# Sprite.net
KiCad netlist of a schematic drawn in EAGLE
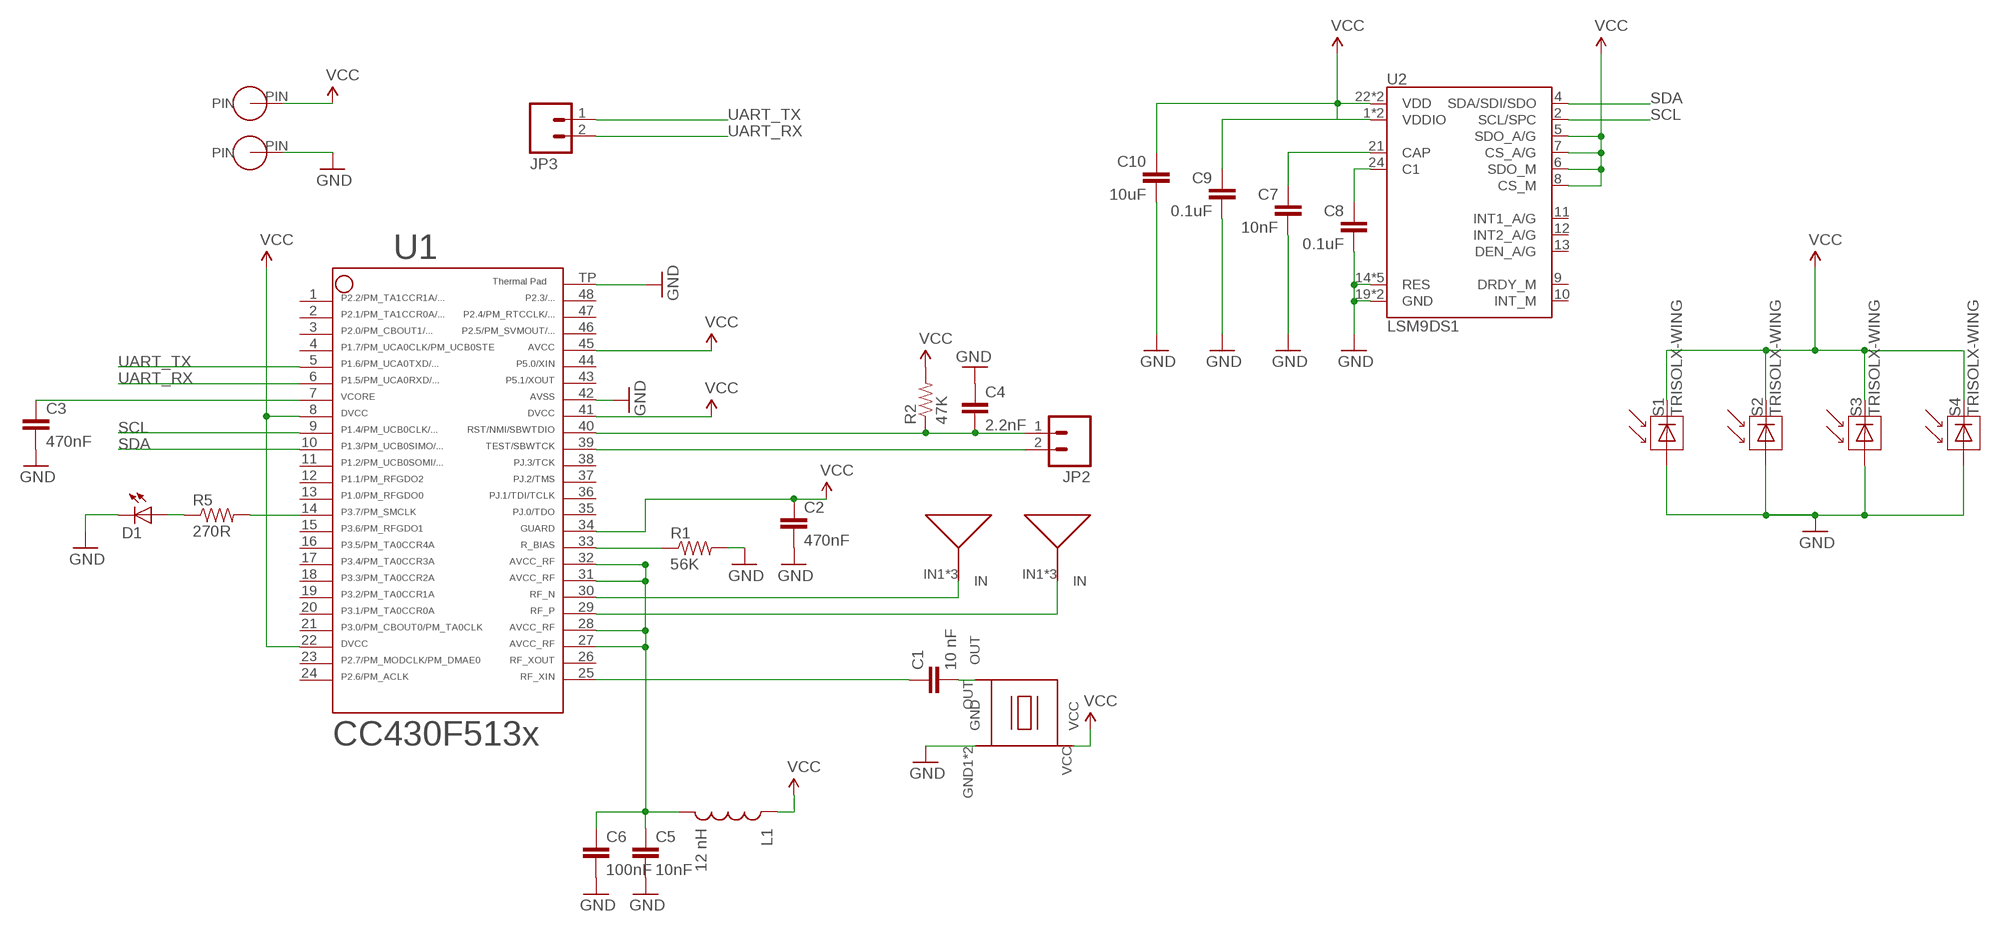
[diagram p0: schematic, sheet 1]

(export (version "E")
  (design (tool "Eeschema 10.0.6"))
  (components
    (comp (ref "ANT-N")
      (value "ANTENNA")
      (footprint "eagle-import:ANTENNA")
      (libsource (lib "eagle-import") (part "ANTENNA"))
    )
    (comp (ref "ANT-P")
      (value "ANTENNA")
      (footprint "eagle-import:ANTENNA")
      (libsource (lib "eagle-import") (part "ANTENNA"))
    )
    (comp (ref "C1")
      (value "10 nF")
      (footprint "eagle-import:0603-CAP")
      (libsource (lib "eagle-import") (part "CAP0603-CAP"))
    )
    (comp (ref "C2")
      (value "470nF")
      (footprint "eagle-import:0603-CAP")
      (libsource (lib "eagle-import") (part "CAP0603-CAP"))
    )
    (comp (ref "C3")
      (value "470nF")
      (footprint "eagle-import:0603-CAP")
      (libsource (lib "eagle-import") (part "CAP0603-CAP"))
    )
    (comp (ref "C4")
      (value "2.2nF")
      (footprint "eagle-import:0603-CAP")
      (libsource (lib "eagle-import") (part "CAP0603-CAP"))
    )
    (comp (ref "C5")
      (value "10nF")
      (footprint "eagle-import:0603-CAP")
      (libsource (lib "eagle-import") (part "CAP0603-CAP"))
    )
    (comp (ref "C6")
      (value "100nF")
      (footprint "eagle-import:0603-CAP")
      (libsource (lib "eagle-import") (part "CAP0603-CAP"))
    )
    (comp (ref "C7")
      (value "10nF")
      (footprint "eagle-import:0603-CAP")
      (libsource (lib "eagle-import") (part "CAP0603-CAP"))
    )
    (comp (ref "C8")
      (value "0.1uF")
      (footprint "eagle-import:0603-CAP")
      (libsource (lib "eagle-import") (part "CAP0603-CAP"))
    )
    (comp (ref "C9")
      (value "0.1uF")
      (footprint "eagle-import:0603-CAP")
      (libsource (lib "eagle-import") (part "CAP0603-CAP"))
    )
    (comp (ref "C10")
      (value "10uF")
      (footprint "eagle-import:0603-CAP")
      (libsource (lib "eagle-import") (part "CAP0603-CAP"))
    )
    (comp (ref "D1")
      (value "LED0603")
      (footprint "eagle-import:LED-0603")
      (libsource (lib "eagle-import") (part "LED0603"))
    )
    (comp (ref "JP2")
      (value "M02PTH")
      (footprint "eagle-import:1X02")
      (libsource (lib "eagle-import") (part "M02PTH"))
    )
    (comp (ref "JP3")
      (value "M02PTH")
      (footprint "eagle-import:1X02")
      (libsource (lib "eagle-import") (part "M02PTH"))
    )
    (comp (ref "L1")
      (value "12 nH")
      (footprint "eagle-import:0603")
      (libsource (lib "eagle-import") (part "INDUCTOR0603"))
    )
    (comp (ref "P1")
      (value "SPRITE_PIN")
      (footprint "eagle-import:SPRITE_PIN")
      (libsource (lib "eagle-import") (part "SPRITE_PIN"))
    )
    (comp (ref "P2")
      (value "SPRITE_PIN")
      (footprint "eagle-import:SPRITE_PIN")
      (libsource (lib "eagle-import") (part "SPRITE_PIN"))
    )
    (comp (ref "R1")
      (value "56K")
      (footprint "eagle-import:0603-RES")
      (libsource (lib "eagle-import") (part "RESISTOR0603-RES"))
    )
    (comp (ref "R2")
      (value "47K")
      (footprint "eagle-import:0603-RES")
      (libsource (lib "eagle-import") (part "RESISTOR0603-RES"))
    )
    (comp (ref "R5")
      (value "270R")
      (footprint "eagle-import:0603-RES")
      (libsource (lib "eagle-import") (part "RESISTOR0603-RES"))
    )
    (comp (ref "S1")
      (value "TRISOLX-WING")
      (footprint "eagle-import:TRISOLX-T01")
      (libsource (lib "eagle-import") (part "TRISOLX-WING"))
    )
    (comp (ref "S2")
      (value "TRISOLX-WING")
      (footprint "eagle-import:TRISOLX-T01")
      (libsource (lib "eagle-import") (part "TRISOLX-WING"))
    )
    (comp (ref "S3")
      (value "TRISOLX-WING")
      (footprint "eagle-import:TRISOLX-T01")
      (libsource (lib "eagle-import") (part "TRISOLX-WING"))
    )
    (comp (ref "S4")
      (value "TRISOLX-WING")
      (footprint "eagle-import:TRISOLX-T01")
      (libsource (lib "eagle-import") (part "TRISOLX-WING"))
    )
    (comp (ref "U1")
      (value "CC430F5137")
      (footprint "eagle-import:RGZ48")
      (libsource (lib "eagle-import") (part "CC430F513X---RGZ48"))
    )
    (comp (ref "U2")
      (value "LSM9DS1")
      (footprint "eagle-import:LGA24-8X4")
      (libsource (lib "eagle-import") (part "LSM9DS1"))
    )
    (comp (ref "X1")
      (value "TCXO_7Z")
      (footprint "eagle-import:TXC_7Z")
      (libsource (lib "eagle-import") (part "TCXO_7Z"))
    )
  )
  (nets
    (net (code "1") (name "GND") (class "Default")
      (node (ref "C10") (pin "2") (pinfunction "2_2") (pintype "passive"))
      (node (ref "C2") (pin "2") (pinfunction "2_2") (pintype "passive"))
      (node (ref "C3") (pin "2") (pinfunction "2_2") (pintype "passive"))
      (node (ref "C4") (pin "1") (pinfunction "1_1") (pintype "passive"))
      (node (ref "C5") (pin "2") (pinfunction "2_2") (pintype "passive"))
      (node (ref "C6") (pin "2") (pinfunction "2_2") (pintype "passive"))
      (node (ref "C7") (pin "2") (pinfunction "2_2") (pintype "passive"))
      (node (ref "C8") (pin "2") (pinfunction "2_2") (pintype "passive"))
      (node (ref "C9") (pin "2") (pinfunction "2_2") (pintype "passive"))
      (node (ref "D1") (pin "C") (pinfunction "C_C") (pintype "passive"))
      (node (ref "P2") (pin "PIN") (pinfunction "PIN_PIN") (pintype "bidirectional"))
      (node (ref "R1") (pin "2") (pinfunction "2_2") (pintype "passive"))
      (node (ref "S1") (pin "P$3") (pinfunction "A_P$3") (pintype "passive"))
      (node (ref "S2") (pin "P$3") (pinfunction "A_P$3") (pintype "passive"))
      (node (ref "S3") (pin "P$3") (pinfunction "A_P$3") (pintype "passive"))
      (node (ref "S4") (pin "P$3") (pinfunction "A_P$3") (pintype "passive"))
      (node (ref "U1") (pin "42") (pinfunction "42_42") (pintype "power_in"))
      (node (ref "U1") (pin "TP") (pinfunction "49_TP") (pintype "power_in"))
      (node (ref "U2") (pin "14") (pinfunction "RES_14") (pintype "bidirectional"))
      (node (ref "U2") (pin "15") (pinfunction "RES_15") (pintype "bidirectional"))
      (node (ref "U2") (pin "16") (pinfunction "RES_16") (pintype "bidirectional"))
      (node (ref "U2") (pin "17") (pinfunction "RES_17") (pintype "bidirectional"))
      (node (ref "U2") (pin "18") (pinfunction "RES_18") (pintype "bidirectional"))
      (node (ref "U2") (pin "19") (pinfunction "GND_19") (pintype "bidirectional"))
      (node (ref "U2") (pin "20") (pinfunction "GND_20") (pintype "bidirectional"))
      (node (ref "X1") (pin "GND1") (pinfunction "GND_GND1") (pintype "bidirectional"))
      (node (ref "X1") (pin "GND2") (pinfunction "GND_GND2") (pintype "bidirectional"))
    )
    (net (code "2") (name "Net-(ANT-N-IN-PadIN1)") (class "Default")
      (node (ref "ANT-N") (pin "IN1") (pinfunction "IN_IN1") (pintype "bidirectional"))
      (node (ref "ANT-N") (pin "IN2") (pinfunction "IN_IN2") (pintype "bidirectional"))
      (node (ref "ANT-N") (pin "IN3") (pinfunction "IN_IN3") (pintype "bidirectional"))
      (node (ref "U1") (pin "30") (pinfunction "30_30") (pintype "bidirectional"))
    )
    (net (code "3") (name "Net-(ANT-P-IN-PadIN1)") (class "Default")
      (node (ref "ANT-P") (pin "IN1") (pinfunction "IN_IN1") (pintype "bidirectional"))
      (node (ref "ANT-P") (pin "IN2") (pinfunction "IN_IN2") (pintype "bidirectional"))
      (node (ref "ANT-P") (pin "IN3") (pinfunction "IN_IN3") (pintype "bidirectional"))
      (node (ref "U1") (pin "29") (pinfunction "29_29") (pintype "bidirectional"))
    )
    (net (code "4") (name "Net-(C1-Pad1)") (class "Default")
      (node (ref "C1") (pin "1") (pinfunction "1_1") (pintype "passive"))
      (node (ref "U1") (pin "25") (pinfunction "25_25") (pintype "input"))
    )
    (net (code "5") (name "Net-(C1-Pad2)") (class "Default")
      (node (ref "C1") (pin "2") (pinfunction "2_2") (pintype "passive"))
      (node (ref "X1") (pin "OUT") (pinfunction "OUT_OUT") (pintype "bidirectional"))
    )
    (net (code "6") (name "Net-(C3-Pad1)") (class "Default")
      (node (ref "C3") (pin "1") (pinfunction "1_1") (pintype "passive"))
      (node (ref "U1") (pin "7") (pinfunction "7_7") (pintype "power_in"))
    )
    (net (code "7") (name "Net-(C4-Pad2)") (class "Default")
      (node (ref "C4") (pin "2") (pinfunction "2_2") (pintype "passive"))
      (node (ref "JP2") (pin "1") (pinfunction "1_1") (pintype "passive"))
      (node (ref "R2") (pin "1") (pinfunction "1_1") (pintype "passive"))
      (node (ref "U1") (pin "40") (pinfunction "40_40") (pintype "bidirectional"))
    )
    (net (code "8") (name "Net-(C5-Pad1)") (class "Default")
      (node (ref "C5") (pin "1") (pinfunction "1_1") (pintype "passive"))
      (node (ref "C6") (pin "1") (pinfunction "1_1") (pintype "passive"))
      (node (ref "L1") (pin "2") (pinfunction "2_2") (pintype "passive"))
      (node (ref "U1") (pin "27") (pinfunction "27_27") (pintype "power_in"))
      (node (ref "U1") (pin "28") (pinfunction "28_28") (pintype "bidirectional"))
      (node (ref "U1") (pin "31") (pinfunction "31_31") (pintype "power_in"))
      (node (ref "U1") (pin "32") (pinfunction "32_32") (pintype "power_in"))
    )
    (net (code "9") (name "Net-(D1-PadA)") (class "Default")
      (node (ref "D1") (pin "A") (pinfunction "A_A") (pintype "passive"))
      (node (ref "R5") (pin "1") (pinfunction "1_1") (pintype "passive"))
    )
    (net (code "10") (name "Net-(JP2-Pad2)") (class "Default")
      (node (ref "JP2") (pin "2") (pinfunction "2_2") (pintype "passive"))
      (node (ref "U1") (pin "39") (pinfunction "39_39") (pintype "input"))
    )
    (net (code "11") (name "Net-(R1-Pad1)") (class "Default")
      (node (ref "R1") (pin "1") (pinfunction "1_1") (pintype "passive"))
      (node (ref "U1") (pin "33") (pinfunction "33_33") (pintype "power_in"))
    )
    (net (code "12") (name "Net-(R5-Pad2)") (class "Default")
      (node (ref "R5") (pin "2") (pinfunction "2_2") (pintype "passive"))
      (node (ref "U1") (pin "14") (pinfunction "14_14") (pintype "bidirectional"))
    )
    (net (code "13") (name "Net-(U2-C1)") (class "Default")
      (node (ref "C8") (pin "1") (pinfunction "1_1") (pintype "passive"))
      (node (ref "U2") (pin "24") (pinfunction "C1_24") (pintype "bidirectional"))
    )
    (net (code "14") (name "Net-(U2-CAP)") (class "Default")
      (node (ref "C7") (pin "1") (pinfunction "1_1") (pintype "passive"))
      (node (ref "U2") (pin "21") (pinfunction "CAP_21") (pintype "bidirectional"))
    )
    (net (code "15") (name "SCL") (class "Default")
      (node (ref "U1") (pin "9") (pinfunction "9_9") (pintype "bidirectional"))
      (node (ref "U2") (pin "2") (pinfunction "SCL/SPC_2") (pintype "bidirectional"))
    )
    (net (code "16") (name "SDA") (class "Default")
      (node (ref "U1") (pin "10") (pinfunction "10_10") (pintype "bidirectional"))
      (node (ref "U2") (pin "4") (pinfunction "SDA/SDI/SDO_4") (pintype "bidirectional"))
    )
    (net (code "17") (name "UART_RX") (class "Default")
      (node (ref "JP3") (pin "2") (pinfunction "2_2") (pintype "passive"))
      (node (ref "U1") (pin "6") (pinfunction "6_6") (pintype "bidirectional"))
    )
    (net (code "18") (name "UART_TX") (class "Default")
      (node (ref "JP3") (pin "1") (pinfunction "1_1") (pintype "passive"))
      (node (ref "U1") (pin "5") (pinfunction "5_5") (pintype "bidirectional"))
    )
    (net (code "19") (name "VCC") (class "Default")
      (node (ref "C10") (pin "1") (pinfunction "1_1") (pintype "passive"))
      (node (ref "C2") (pin "1") (pinfunction "1_1") (pintype "passive"))
      (node (ref "C9") (pin "1") (pinfunction "1_1") (pintype "passive"))
      (node (ref "L1") (pin "1") (pinfunction "1_1") (pintype "passive"))
      (node (ref "P1") (pin "PIN") (pinfunction "PIN_PIN") (pintype "bidirectional"))
      (node (ref "R2") (pin "2") (pinfunction "2_2") (pintype "passive"))
      (node (ref "S1") (pin "P$2") (pinfunction "C_P$2") (pintype "passive"))
      (node (ref "S2") (pin "P$2") (pinfunction "C_P$2") (pintype "passive"))
      (node (ref "S3") (pin "P$2") (pinfunction "C_P$2") (pintype "passive"))
      (node (ref "S4") (pin "P$2") (pinfunction "C_P$2") (pintype "passive"))
      (node (ref "U1") (pin "22") (pinfunction "22_22") (pintype "power_in"))
      (node (ref "U1") (pin "34") (pinfunction "34_34") (pintype "power_in"))
      (node (ref "U1") (pin "41") (pinfunction "41_41") (pintype "power_in"))
      (node (ref "U1") (pin "45") (pinfunction "45_45") (pintype "input"))
      (node (ref "U1") (pin "8") (pinfunction "8_8") (pintype "power_in"))
      (node (ref "U2") (pin "1") (pinfunction "VDDIO_1") (pintype "bidirectional"))
      (node (ref "U2") (pin "22") (pinfunction "VDD_22") (pintype "bidirectional"))
      (node (ref "U2") (pin "23") (pinfunction "VDD_23") (pintype "bidirectional"))
      (node (ref "U2") (pin "3") (pinfunction "VDDIO_3") (pintype "bidirectional"))
      (node (ref "U2") (pin "5") (pinfunction "SDO_A/G_5") (pintype "bidirectional"))
      (node (ref "U2") (pin "6") (pinfunction "SDO_M_6") (pintype "bidirectional"))
      (node (ref "U2") (pin "7") (pinfunction "CS_A/G_7") (pintype "bidirectional"))
      (node (ref "U2") (pin "8") (pinfunction "CS_M_8") (pintype "bidirectional"))
      (node (ref "X1") (pin "VCC") (pinfunction "VCC_VCC") (pintype "bidirectional"))
    )
    (net (code "20") (name "unconnected-(U1-Pad1)") (class "Default")
      (node (ref "U1") (pin "1") (pinfunction "1_1") (pintype "bidirectional"))
    )
    (net (code "21") (name "unconnected-(U1-Pad2)") (class "Default")
      (node (ref "U1") (pin "2") (pinfunction "2_2") (pintype "bidirectional"))
    )
    (net (code "22") (name "unconnected-(U1-Pad3)") (class "Default")
      (node (ref "U1") (pin "3") (pinfunction "3_3") (pintype "bidirectional"))
    )
    (net (code "23") (name "unconnected-(U1-Pad4)") (class "Default")
      (node (ref "U1") (pin "4") (pinfunction "4_4") (pintype "bidirectional"))
    )
    (net (code "24") (name "unconnected-(U1-Pad11)") (class "Default")
      (node (ref "U1") (pin "11") (pinfunction "11_11") (pintype "bidirectional"))
    )
    (net (code "25") (name "unconnected-(U1-Pad12)") (class "Default")
      (node (ref "U1") (pin "12") (pinfunction "12_12") (pintype "bidirectional"))
    )
    (net (code "26") (name "unconnected-(U1-Pad13)") (class "Default")
      (node (ref "U1") (pin "13") (pinfunction "13_13") (pintype "bidirectional"))
    )
    (net (code "27") (name "unconnected-(U1-Pad15)") (class "Default")
      (node (ref "U1") (pin "15") (pinfunction "15_15") (pintype "bidirectional"))
    )
    (net (code "28") (name "unconnected-(U1-Pad16)") (class "Default")
      (node (ref "U1") (pin "16") (pinfunction "16_16") (pintype "bidirectional"))
    )
    (net (code "29") (name "unconnected-(U1-Pad17)") (class "Default")
      (node (ref "U1") (pin "17") (pinfunction "17_17") (pintype "bidirectional"))
    )
    (net (code "30") (name "unconnected-(U1-Pad18)") (class "Default")
      (node (ref "U1") (pin "18") (pinfunction "18_18") (pintype "bidirectional"))
    )
    (net (code "31") (name "unconnected-(U1-Pad19)") (class "Default")
      (node (ref "U1") (pin "19") (pinfunction "19_19") (pintype "bidirectional"))
    )
    (net (code "32") (name "unconnected-(U1-Pad20)") (class "Default")
      (node (ref "U1") (pin "20") (pinfunction "20_20") (pintype "bidirectional"))
    )
    (net (code "33") (name "unconnected-(U1-Pad21)") (class "Default")
      (node (ref "U1") (pin "21") (pinfunction "21_21") (pintype "bidirectional"))
    )
    (net (code "34") (name "unconnected-(U1-Pad23)") (class "Default")
      (node (ref "U1") (pin "23") (pinfunction "23_23") (pintype "bidirectional"))
    )
    (net (code "35") (name "unconnected-(U1-Pad24)") (class "Default")
      (node (ref "U1") (pin "24") (pinfunction "24_24") (pintype "bidirectional"))
    )
    (net (code "36") (name "unconnected-(U1-Pad26)") (class "Default")
      (node (ref "U1") (pin "26") (pinfunction "26_26") (pintype "output"))
    )
    (net (code "37") (name "unconnected-(U1-Pad35)") (class "Default")
      (node (ref "U1") (pin "35") (pinfunction "35_35") (pintype "bidirectional"))
    )
    (net (code "38") (name "unconnected-(U1-Pad36)") (class "Default")
      (node (ref "U1") (pin "36") (pinfunction "36_36") (pintype "bidirectional"))
    )
    (net (code "39") (name "unconnected-(U1-Pad37)") (class "Default")
      (node (ref "U1") (pin "37") (pinfunction "37_37") (pintype "bidirectional"))
    )
    (net (code "40") (name "unconnected-(U1-Pad38)") (class "Default")
      (node (ref "U1") (pin "38") (pinfunction "38_38") (pintype "bidirectional"))
    )
    (net (code "41") (name "unconnected-(U1-Pad43)") (class "Default")
      (node (ref "U1") (pin "43") (pinfunction "43_43") (pintype "input"))
    )
    (net (code "42") (name "unconnected-(U1-Pad44)") (class "Default")
      (node (ref "U1") (pin "44") (pinfunction "44_44") (pintype "input"))
    )
    (net (code "43") (name "unconnected-(U1-Pad46)") (class "Default")
      (node (ref "U1") (pin "46") (pinfunction "46_46") (pintype "bidirectional"))
    )
    (net (code "44") (name "unconnected-(U1-Pad47)") (class "Default")
      (node (ref "U1") (pin "47") (pinfunction "47_47") (pintype "input"))
    )
    (net (code "45") (name "unconnected-(U1-Pad48)") (class "Default")
      (node (ref "U1") (pin "48") (pinfunction "48_48") (pintype "bidirectional"))
    )
    (net (code "46") (name "unconnected-(U2-DEN_A{slash}G-Pad13)") (class "Default")
      (node (ref "U2") (pin "13") (pinfunction "DEN_A/G_13") (pintype "bidirectional"))
    )
    (net (code "47") (name "unconnected-(U2-DRDY_M-Pad9)") (class "Default")
      (node (ref "U2") (pin "9") (pinfunction "DRDY_M_9") (pintype "bidirectional"))
    )
    (net (code "48") (name "unconnected-(U2-INT1_A{slash}G-Pad11)") (class "Default")
      (node (ref "U2") (pin "11") (pinfunction "INT1_A/G_11") (pintype "bidirectional"))
    )
    (net (code "49") (name "unconnected-(U2-INT2_A{slash}G-Pad12)") (class "Default")
      (node (ref "U2") (pin "12") (pinfunction "INT2_A/G_12") (pintype "bidirectional"))
    )
    (net (code "50") (name "unconnected-(U2-INT_M-Pad10)") (class "Default")
      (node (ref "U2") (pin "10") (pinfunction "INT_M_10") (pintype "bidirectional"))
    )
  )
)
